# PowerReg.net
KiCad netlist of a schematic drawn in Altium Designer
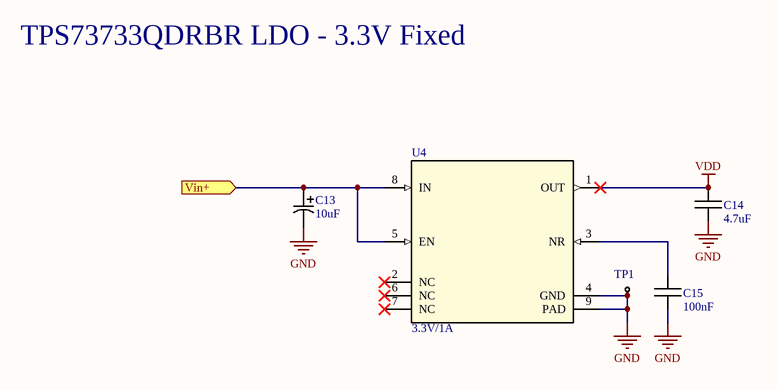
[diagram p0: PowerReg.SchDoc]

(export (version "E")
  (design (tool "Eeschema 10.0.6"))
  (components
    (comp (ref "C13")
      (value "10uF")
      (footprint "CAP1206_TAJA")
      (description "Cap Tant Solid 10uF 16V A CASE 10%( 3.2 X 1.6 X 1.6mm) Inward L SMD 3216-18 3 Ohm 125C T/R")
      (fields
        (field (name "MANUFACTURER_PART_NUMBER") "TAJA106K016RNJ")
        (field (name "MANUFACTURER") "Kyocera AVX")
        (field (name "COPYRIGHT") "Copyright (C) 2023 Ultra Librarian. All rights reserved.")
      )
      (libsource (lib "Schlib1") (part "TAJA106K016RNJ"))
    )
    (comp (ref "C14")
      (value "4.7uF")
      (footprint "CAP0805")
      (description "Multilayer Ceramic Capacitor, 4.7 uF, 25 V, ± 10%, X5R, 0805 [2012 Metric]")
      (fields
        (field (name "MANUFACTURER") "Samsung")
        (field (name "MANUFACTURER PART NUMBER") "CL21A475KAQNNNE")
      )
      (libsource (lib "Schlib1") (part "CL21A475KAQNNNE"))
    )
    (comp (ref "C15")
      (value "100nF")
      (footprint "CAP0805")
      (description "Multilayer Ceramic Capacitor, 0.1 uF, 50 V, ± 10%, X7R, 0805 [2012 Metric]")
      (fields
        (field (name "MANUFACTURER") "Yageo")
        (field (name "MANUFACTURER PART NUMBER") "CC0805KRX7R9BB104")
      )
      (libsource (lib "Schlib1") (part "CC0805KRX7R9BB104"))
    )
    (comp (ref "TP1")
      (value "1mm Test Point")
      (footprint "TP_1MM")
      (libsource (lib "Schlib1") (part "TestPoint_1mm"))
    )
    (comp (ref "U4")
      (value "3.3V/1A")
      (footprint "VSON_DRB8")
      (description "Automotive 1-A, ultra-low-dropout voltage regulator with reverse current protection & enable")
      (fields
        (field (name "MANUFACTURER") "Texas Instruments")
        (field (name "MANUFACTURER PART NUMBER") "TPS73733QDRBRQ1")
      )
      (libsource (lib "Schlib1") (part "TPS73733QDRBRQ1"))
    )
  )
  (nets
    (net (code "1") (name "/Vin+") (class "Default")
      (node (ref "C13") (pin "1") (pinfunction "1_1") (pintype "passive"))
      (node (ref "U4") (pin "5") (pinfunction "EN_5") (pintype "input"))
      (node (ref "U4") (pin "8") (pinfunction "IN_8") (pintype "input"))
    )
    (net (code "2") (name "GND") (class "Default")
      (node (ref "C13") (pin "2") (pinfunction "2_2") (pintype "passive"))
      (node (ref "C14") (pin "1") (pinfunction "1_1") (pintype "passive"))
      (node (ref "C15") (pin "2") (pinfunction "2_2") (pintype "passive"))
      (node (ref "TP1") (pin "1") (pinfunction "0_1") (pintype "passive"))
      (node (ref "U4") (pin "4") (pinfunction "GND_4") (pintype "power_in"))
      (node (ref "U4") (pin "9") (pinfunction "PAD_9") (pintype "power_in"))
    )
    (net (code "3") (name "Net-(U4-NR)") (class "Default")
      (node (ref "C15") (pin "1") (pinfunction "1_1") (pintype "passive"))
      (node (ref "U4") (pin "3") (pinfunction "NR_3") (pintype "input"))
    )
    (net (code "4") (name "VDD") (class "Default")
      (node (ref "C14") (pin "2") (pinfunction "2_2") (pintype "passive"))
      (node (ref "U4") (pin "1") (pinfunction "OUT_1") (pintype "output"))
    )
    (net (code "5") (name "unconnected-(U4-NC-Pad2)") (class "Default")
      (node (ref "U4") (pin "2") (pinfunction "NC_2") (pintype "passive+no_connect"))
    )
    (net (code "6") (name "unconnected-(U4-NC-Pad6)") (class "Default")
      (node (ref "U4") (pin "6") (pinfunction "NC_6") (pintype "passive+no_connect"))
    )
    (net (code "7") (name "unconnected-(U4-NC-Pad7)") (class "Default")
      (node (ref "U4") (pin "7") (pinfunction "NC_7") (pintype "passive+no_connect"))
    )
  )
)
